# BatteryProtection.net
KiCad netlist of a schematic drawn in EAGLE
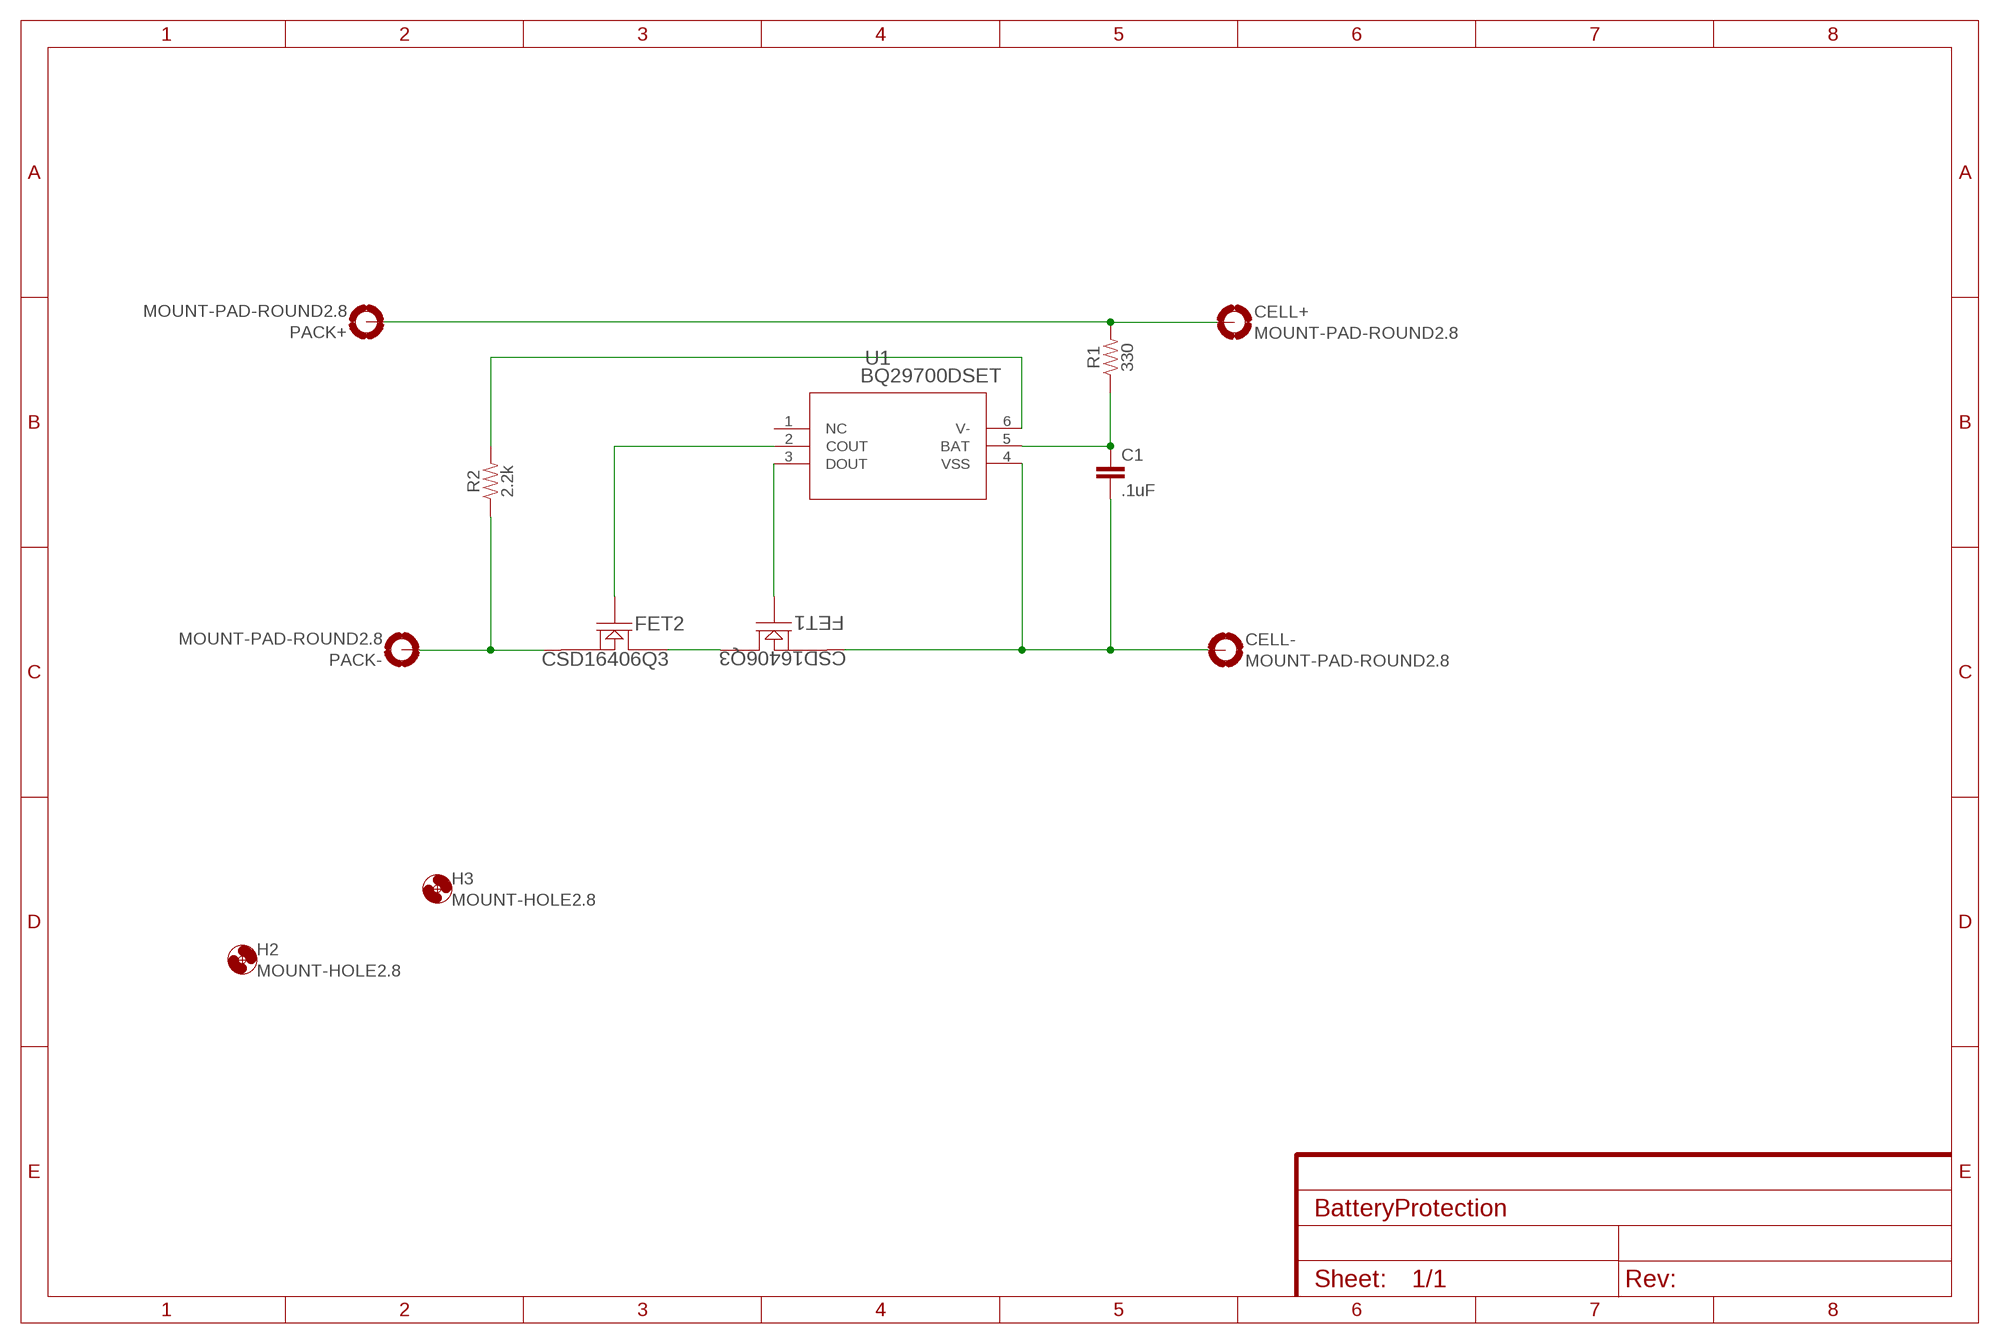
[diagram p0: schematic, sheet 1]

(export (version "E")
  (design (tool "Eeschema 10.0.6"))
  (components
    (comp (ref "C1")
      (value ".1uF")
      (footprint "eagle-import:0805")
      (libsource (lib "eagle-import") (part "0.33UF/330NF-0805-50V-10%"))
    )
    (comp (ref "CELL+")
      (value "MOUNT-PAD-ROUND2.8")
      (footprint "eagle-import:2,8-PAD")
      (libsource (lib "eagle-import") (part "MOUNT-PAD-ROUND2.8"))
    )
    (comp (ref "CELL-")
      (value "MOUNT-PAD-ROUND2.8")
      (footprint "eagle-import:2,8-PAD")
      (libsource (lib "eagle-import") (part "MOUNT-PAD-ROUND2.8"))
    )
    (comp (ref "FET1")
      (value "CSD16406Q3")
      (footprint "eagle-import:DQG0008A")
      (libsource (lib "eagle-import") (part "CSD16406Q3"))
    )
    (comp (ref "FET2")
      (value "CSD16406Q3")
      (footprint "eagle-import:DQG0008A")
      (libsource (lib "eagle-import") (part "CSD16406Q3"))
    )
    (comp (ref "H2")
      (value "MOUNT-HOLE2.8")
      (footprint "eagle-import:2,8")
      (libsource (lib "eagle-import") (part "MOUNT-HOLE2.8"))
    )
    (comp (ref "H3")
      (value "MOUNT-HOLE2.8")
      (footprint "eagle-import:2,8")
      (libsource (lib "eagle-import") (part "MOUNT-HOLE2.8"))
    )
    (comp (ref "PACK+")
      (value "MOUNT-PAD-ROUND2.8")
      (footprint "eagle-import:2,8-PAD")
      (libsource (lib "eagle-import") (part "MOUNT-PAD-ROUND2.8"))
    )
    (comp (ref "PACK-")
      (value "MOUNT-PAD-ROUND2.8")
      (footprint "eagle-import:2,8-PAD")
      (libsource (lib "eagle-import") (part "MOUNT-PAD-ROUND2.8"))
    )
    (comp (ref "R1")
      (value "330")
      (footprint "eagle-import:0603")
      (libsource (lib "eagle-import") (part "33KOHM-0603-1/10W-1%"))
    )
    (comp (ref "R2")
      (value "2.2k")
      (footprint "eagle-import:0603")
      (libsource (lib "eagle-import") (part "33KOHM-0603-1/10W-1%"))
    )
    (comp (ref "U1")
      (value "BQ29700DSET")
      (footprint "eagle-import:DSE6")
      (libsource (lib "eagle-import") (part "BQ29700DSET"))
    )
  )
  (nets
    (net (code "1") (name "Net-(CELL+-MOUNT)") (class "Default")
      (node (ref "CELL+") (pin "B2,8") (pinfunction "MOUNT_B2,8") (pintype "passive"))
      (node (ref "PACK+") (pin "B2,8") (pinfunction "MOUNT_B2,8") (pintype "passive"))
      (node (ref "R1") (pin "2") (pinfunction "2_2") (pintype "passive"))
    )
    (net (code "2") (name "Net-(CELL--MOUNT)") (class "Default")
      (node (ref "C1") (pin "2") (pinfunction "2_2") (pintype "passive"))
      (node (ref "CELL-") (pin "B2,8") (pinfunction "MOUNT_B2,8") (pintype "passive"))
      (node (ref "FET1") (pin "1") (pinfunction "SOURCE_1") (pintype "passive"))
      (node (ref "U1") (pin "4") (pinfunction "VSS_4") (pintype "power_in"))
    )
    (net (code "3") (name "Net-(FET1-DRAIN_2)") (class "Default")
      (node (ref "FET1") (pin "5") (pinfunction "DRAIN_2_5") (pintype "passive"))
      (node (ref "FET2") (pin "5") (pinfunction "DRAIN_2_5") (pintype "passive"))
    )
    (net (code "4") (name "Net-(FET1-GATE)") (class "Default")
      (node (ref "FET1") (pin "4") (pinfunction "GATE_4") (pintype "passive"))
      (node (ref "U1") (pin "3") (pinfunction "DOUT_3") (pintype "output"))
    )
    (net (code "5") (name "Net-(FET2-GATE)") (class "Default")
      (node (ref "FET2") (pin "4") (pinfunction "GATE_4") (pintype "passive"))
      (node (ref "U1") (pin "2") (pinfunction "COUT_2") (pintype "output"))
    )
    (net (code "6") (name "Net-(FET2-SOURCE)") (class "Default")
      (node (ref "FET2") (pin "1") (pinfunction "SOURCE_1") (pintype "passive"))
      (node (ref "PACK-") (pin "B2,8") (pinfunction "MOUNT_B2,8") (pintype "passive"))
      (node (ref "R2") (pin "1") (pinfunction "1_1") (pintype "passive"))
    )
    (net (code "7") (name "Net-(U1-BAT)") (class "Default")
      (node (ref "C1") (pin "1") (pinfunction "1_1") (pintype "passive"))
      (node (ref "R1") (pin "1") (pinfunction "1_1") (pintype "passive"))
      (node (ref "U1") (pin "5") (pinfunction "BAT_5") (pintype "power_in"))
    )
    (net (code "8") (name "Net-(U1-V-)") (class "Default")
      (node (ref "R2") (pin "2") (pinfunction "2_2") (pintype "passive"))
      (node (ref "U1") (pin "6") (pinfunction "V-_6") (pintype "power_in"))
    )
    (net (code "9") (name "unconnected-(U1-NC-Pad1)") (class "Default")
      (node (ref "U1") (pin "1") (pinfunction "NC_1") (pintype "no_connect"))
    )
  )
)
